# 03_-_PWR_3V3_1V0.net
KiCad netlist of a schematic drawn in Altium Designer
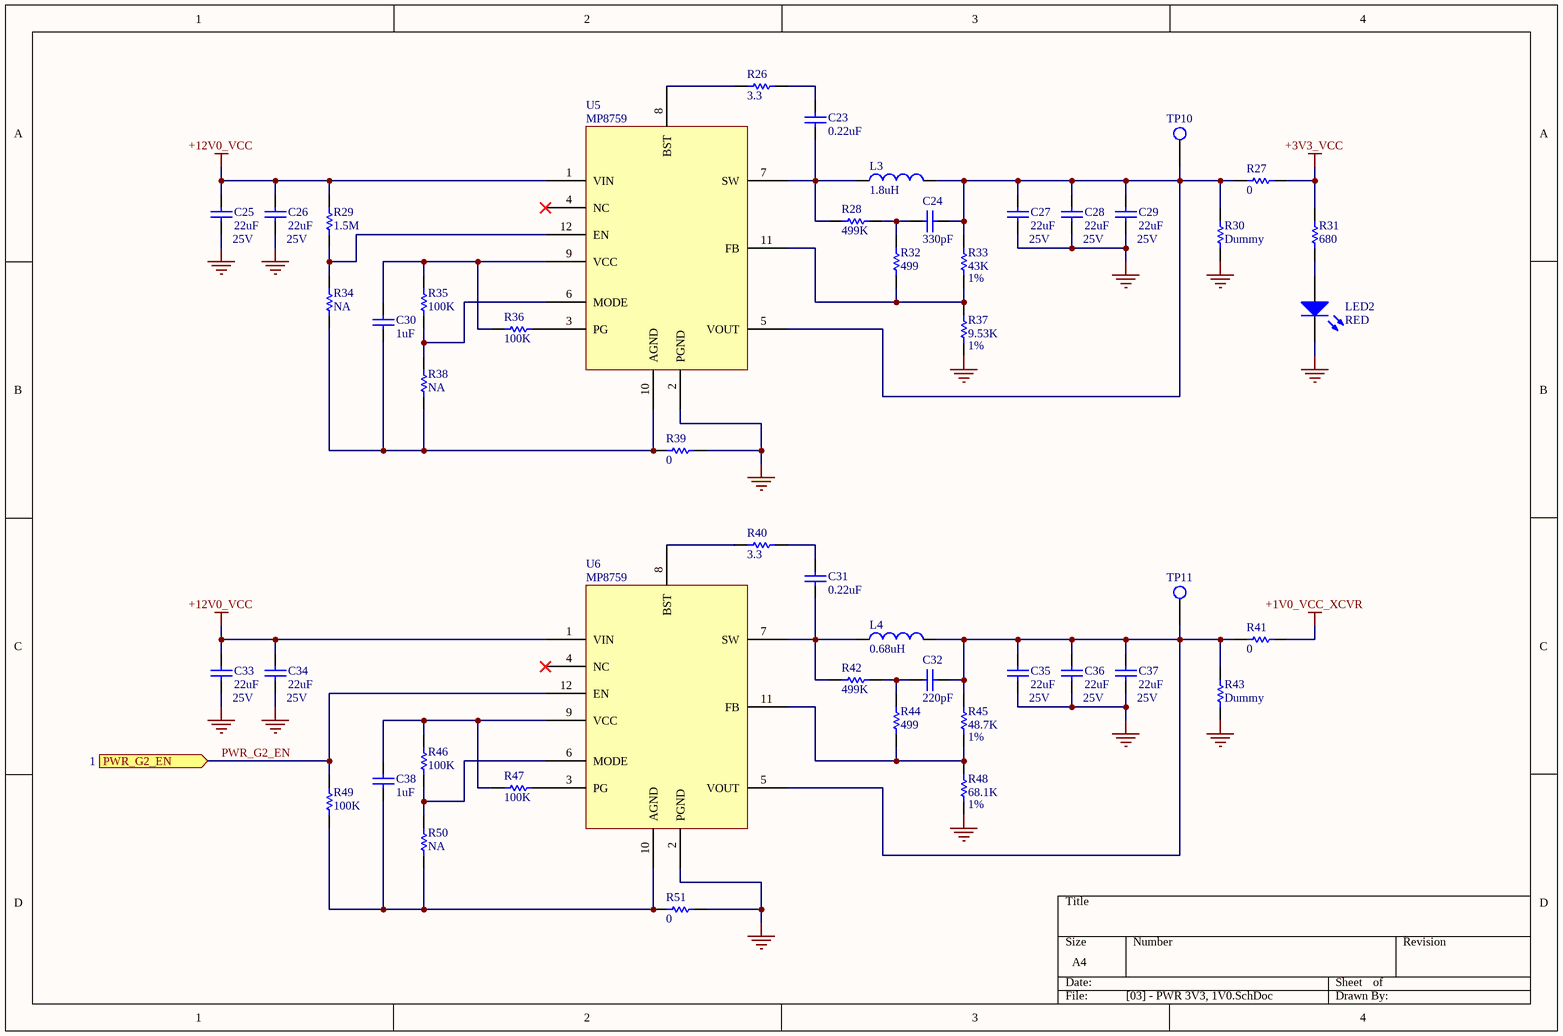
[diagram p0: [03] - PWR 3V3, 1V0.SchDoc]

(export (version "E")
  (design (tool "Eeschema 10.0.6"))
  (components
    (comp (ref "C23")
      (value "0.22uF")
      (footprint "0402_C")
      (description "Non-Pol SMD Capacitor")
      (libsource (lib "Passive Components") (part "Cap SMD"))
    )
    (comp (ref "C24")
      (value "330pF")
      (footprint "0402_C")
      (description "Non-Pol SMD Capacitor")
      (libsource (lib "Passive Components") (part "Cap SMD"))
    )
    (comp (ref "C25")
      (value "22uF")
      (footprint "1210_C")
      (description "Non-Pol SMD Capacitor")
      (fields (field (name "RATED_VOLTAGE") "25V") (field (name "MANUFACTURER PART NUM") "GRM32ER71E226KE15"))
      (libsource (lib "Passive Components") (part "Cap SMD"))
    )
    (comp (ref "C26")
      (value "22uF")
      (footprint "1210_C")
      (description "Non-Pol SMD Capacitor")
      (fields (field (name "RATED_VOLTAGE") "25V") (field (name "MANUFACTURER PART NUM") "GRM32ER71E226KE15"))
      (libsource (lib "Passive Components") (part "Cap SMD"))
    )
    (comp (ref "C27")
      (value "22uF")
      (footprint "1210_C")
      (description "Non-Pol SMD Capacitor")
      (fields (field (name "RATED_VOLTAGE") "25V") (field (name "MANUFACTURER PART NUM") "GRM32ER71E226KE15"))
      (libsource (lib "Passive Components") (part "Cap SMD"))
    )
    (comp (ref "C28")
      (value "22uF")
      (footprint "1210_C")
      (description "Non-Pol SMD Capacitor")
      (fields (field (name "RATED_VOLTAGE") "25V") (field (name "MANUFACTURER PART NUM") "GRM32ER71E226KE15"))
      (libsource (lib "Passive Components") (part "Cap SMD"))
    )
    (comp (ref "C29")
      (value "22uF")
      (footprint "1210_C")
      (description "Non-Pol SMD Capacitor")
      (fields (field (name "RATED_VOLTAGE") "25V") (field (name "MANUFACTURER PART NUM") "GRM32ER71E226KE15"))
      (libsource (lib "Passive Components") (part "Cap SMD"))
    )
    (comp (ref "C30")
      (value "1uF")
      (footprint "0402_C")
      (description "Non-Pol SMD Capacitor")
      (fields (field (name "MANUFACTURER PART NUM") "GCM155C71A105ME38"))
      (libsource (lib "Passive Components") (part "Cap SMD"))
    )
    (comp (ref "C31")
      (value "0.22uF")
      (footprint "0402_C")
      (description "Non-Pol SMD Capacitor")
      (libsource (lib "Passive Components") (part "Cap SMD"))
    )
    (comp (ref "C32")
      (value "220pF")
      (footprint "0402_C")
      (description "Non-Pol SMD Capacitor")
      (libsource (lib "Passive Components") (part "Cap SMD"))
    )
    (comp (ref "C33")
      (value "22uF")
      (footprint "1210_C")
      (description "Non-Pol SMD Capacitor")
      (fields (field (name "RATED_VOLTAGE") "25V") (field (name "MANUFACTURER PART NUM") "GRM32ER71E226KE15"))
      (libsource (lib "Passive Components") (part "Cap SMD"))
    )
    (comp (ref "C34")
      (value "22uF")
      (footprint "1210_C")
      (description "Non-Pol SMD Capacitor")
      (fields (field (name "RATED_VOLTAGE") "25V") (field (name "MANUFACTURER PART NUM") "GRM32ER71E226KE15"))
      (libsource (lib "Passive Components") (part "Cap SMD"))
    )
    (comp (ref "C35")
      (value "22uF")
      (footprint "1210_C")
      (description "Non-Pol SMD Capacitor")
      (fields (field (name "RATED_VOLTAGE") "25V") (field (name "MANUFACTURER PART NUM") "GRM32ER71E226KE15"))
      (libsource (lib "Passive Components") (part "Cap SMD"))
    )
    (comp (ref "C36")
      (value "22uF")
      (footprint "1210_C")
      (description "Non-Pol SMD Capacitor")
      (fields (field (name "RATED_VOLTAGE") "25V") (field (name "MANUFACTURER PART NUM") "GRM32ER71E226KE15"))
      (libsource (lib "Passive Components") (part "Cap SMD"))
    )
    (comp (ref "C37")
      (value "22uF")
      (footprint "1210_C")
      (description "Non-Pol SMD Capacitor")
      (fields (field (name "RATED_VOLTAGE") "25V") (field (name "MANUFACTURER PART NUM") "GRM32ER71E226KE15"))
      (libsource (lib "Passive Components") (part "Cap SMD"))
    )
    (comp (ref "C38")
      (value "1uF")
      (footprint "0402_C")
      (description "Non-Pol SMD Capacitor")
      (fields (field (name "MANUFACTURER PART NUM") "GCM155C71A105ME38"))
      (libsource (lib "Passive Components") (part "Cap SMD"))
    )
    (comp (ref "L3")
      (value "1.8uH")
      (footprint "IHLP-4040")
      (description "Inductor SMD")
      (fields (field (name "MANUFACTURER PART NUM") "IHLP4040DZER1R8M11"))
      (libsource (lib "Passive Components") (part "Inductor"))
    )
    (comp (ref "L4")
      (value "0.68uH")
      (footprint "IHLP-2525")
      (description "Inductor SMD")
      (fields (field (name "MANUFACTURER PART NUM") "IHLP2525CZERR68M01"))
      (libsource (lib "Passive Components") (part "Inductor"))
    )
    (comp (ref "LED2")
      (value "RED")
      (footprint "LED_0805")
      (description "Typical LED")
      (libsource (lib "Common Components") (part "LED"))
    )
    (comp (ref "R26")
      (value "3.3")
      (footprint "0402_R")
      (description "SMD Resistor")
      (fields (field (name "TOLERANCE") "5%"))
      (libsource (lib "Passive Components") (part "Res SMD"))
    )
    (comp (ref "R27")
      (value "0")
      (footprint "1210_R")
      (description "SMD Resistor")
      (fields (field (name "TOLERANCE") "5%"))
      (libsource (lib "Passive Components") (part "Res SMD"))
    )
    (comp (ref "R28")
      (value "499K")
      (footprint "0402_R")
      (description "SMD Resistor")
      (fields (field (name "TOLERANCE") "1%"))
      (libsource (lib "Passive Components") (part "Res SMD"))
    )
    (comp (ref "R29")
      (value "1.5M")
      (footprint "0402_R")
      (description "SMD Resistor")
      (fields (field (name "TOLERANCE") "5%"))
      (libsource (lib "Passive Components") (part "Res SMD"))
    )
    (comp (ref "R30")
      (value "Dummy")
      (footprint "1210_R")
      (description "SMD Resistor")
      (fields (field (name "TOLERANCE") "5%"))
      (libsource (lib "Passive Components") (part "Res SMD"))
    )
    (comp (ref "R31")
      (value "680")
      (footprint "0805_R")
      (description "SMD Resistor")
      (fields (field (name "TOLERANCE") "5%"))
      (libsource (lib "Passive Components") (part "Res SMD"))
    )
    (comp (ref "R32")
      (value "499")
      (footprint "0402_R")
      (description "SMD Resistor")
      (fields (field (name "TOLERANCE") "1%"))
      (libsource (lib "Passive Components") (part "Res SMD"))
    )
    (comp (ref "R33")
      (value "43K")
      (footprint "0402_R")
      (description "SMD Resistor")
      (fields (field (name "TOLERANCE") "1%"))
      (libsource (lib "Passive Components") (part "Res SMD"))
    )
    (comp (ref "R34")
      (value "NA")
      (footprint "0402_R")
      (description "SMD Resistor")
      (fields (field (name "TOLERANCE") "5%"))
      (libsource (lib "Passive Components") (part "Res SMD"))
    )
    (comp (ref "R35")
      (value "100K")
      (footprint "0402_R")
      (description "SMD Resistor")
      (fields (field (name "TOLERANCE") "5%"))
      (libsource (lib "Passive Components") (part "Res SMD"))
    )
    (comp (ref "R36")
      (value "100K")
      (footprint "0402_R")
      (description "SMD Resistor")
      (fields (field (name "TOLERANCE") "5%"))
      (libsource (lib "Passive Components") (part "Res SMD"))
    )
    (comp (ref "R37")
      (value "9.53K")
      (footprint "0402_R")
      (description "SMD Resistor")
      (fields (field (name "TOLERANCE") "1%"))
      (libsource (lib "Passive Components") (part "Res SMD"))
    )
    (comp (ref "R38")
      (value "NA")
      (footprint "0402_R")
      (description "SMD Resistor")
      (fields (field (name "TOLERANCE") "5%"))
      (libsource (lib "Passive Components") (part "Res SMD"))
    )
    (comp (ref "R39")
      (value "0")
      (footprint "0402_R")
      (description "SMD Resistor")
      (fields (field (name "TOLERANCE") "5%"))
      (libsource (lib "Passive Components") (part "Res SMD"))
    )
    (comp (ref "R40")
      (value "3.3")
      (footprint "0402_R")
      (description "SMD Resistor")
      (fields (field (name "TOLERANCE") "5%"))
      (libsource (lib "Passive Components") (part "Res SMD"))
    )
    (comp (ref "R41")
      (value "0")
      (footprint "1210_R")
      (description "SMD Resistor")
      (fields (field (name "TOLERANCE") "5%"))
      (libsource (lib "Passive Components") (part "Res SMD"))
    )
    (comp (ref "R42")
      (value "499K")
      (footprint "0402_R")
      (description "SMD Resistor")
      (fields (field (name "TOLERANCE") "1%"))
      (libsource (lib "Passive Components") (part "Res SMD"))
    )
    (comp (ref "R43")
      (value "Dummy")
      (footprint "1210_R")
      (description "SMD Resistor")
      (fields (field (name "TOLERANCE") "5%"))
      (libsource (lib "Passive Components") (part "Res SMD"))
    )
    (comp (ref "R44")
      (value "499")
      (footprint "0402_R")
      (description "SMD Resistor")
      (fields (field (name "TOLERANCE") "1%"))
      (libsource (lib "Passive Components") (part "Res SMD"))
    )
    (comp (ref "R45")
      (value "48.7K")
      (footprint "0402_R")
      (description "SMD Resistor")
      (fields (field (name "TOLERANCE") "1%"))
      (libsource (lib "Passive Components") (part "Res SMD"))
    )
    (comp (ref "R46")
      (value "100K")
      (footprint "0402_R")
      (description "SMD Resistor")
      (fields (field (name "TOLERANCE") "5%"))
      (libsource (lib "Passive Components") (part "Res SMD"))
    )
    (comp (ref "R47")
      (value "100K")
      (footprint "0402_R")
      (description "SMD Resistor")
      (fields (field (name "TOLERANCE") "5%"))
      (libsource (lib "Passive Components") (part "Res SMD"))
    )
    (comp (ref "R48")
      (value "68.1K")
      (footprint "0402_R")
      (description "SMD Resistor")
      (fields (field (name "TOLERANCE") "1%"))
      (libsource (lib "Passive Components") (part "Res SMD"))
    )
    (comp (ref "R49")
      (value "100K")
      (footprint "0402_R")
      (description "SMD Resistor")
      (fields (field (name "TOLERANCE") "5%"))
      (libsource (lib "Passive Components") (part "Res SMD"))
    )
    (comp (ref "R50")
      (value "NA")
      (footprint "0402_R")
      (description "SMD Resistor")
      (fields (field (name "TOLERANCE") "5%"))
      (libsource (lib "Passive Components") (part "Res SMD"))
    )
    (comp (ref "R51")
      (value "0")
      (footprint "0402_R")
      (description "SMD Resistor")
      (fields (field (name "TOLERANCE") "5%"))
      (libsource (lib "Passive Components") (part "Res SMD"))
    )
    (comp (ref "TP10")
      (value "Test Point")
      (footprint "PIN_1.5mm")
      (description "Test Point Footprint")
      (libsource (lib "Passive Components") (part "Test Point"))
    )
    (comp (ref "TP11")
      (value "Test Point")
      (footprint "PIN_1.5mm")
      (description "Test Point Footprint")
      (libsource (lib "Passive Components") (part "Test Point"))
    )
    (comp (ref "U5")
      (value "MP8759")
      (description "26V, 8A, Low I Q , High-Current,  Synchronous, Step-Down Converter")
      (fields (field (name "MANUFACTURER PART NUM") "MP8759GD"))
      (libsource (lib "Project_schlib") (part "MP8759"))
    )
    (comp (ref "U6")
      (value "MP8759")
      (description "26V, 8A, Low I Q , High-Current,  Synchronous, Step-Down Converter")
      (fields (field (name "MANUFACTURER PART NUM") "MP8759GD"))
      (libsource (lib "Project_schlib") (part "MP8759"))
    )
  )
  (nets
    (net (code "1") (name "+1V0_VCC_XCVR") (class "Default")
      (node (ref "R41") (pin "2") (pinfunction "2_2") (pintype "passive"))
    )
    (net (code "2") (name "+3V3_VCC") (class "Default")
      (node (ref "R27") (pin "2") (pinfunction "2_2") (pintype "passive"))
      (node (ref "R31") (pin "2") (pinfunction "2_2") (pintype "passive"))
    )
    (net (code "3") (name "+12V0_VCC") (class "Default")
      (node (ref "C25") (pin "2") (pinfunction "2_2") (pintype "passive"))
      (node (ref "C26") (pin "2") (pinfunction "2_2") (pintype "passive"))
      (node (ref "C33") (pin "2") (pinfunction "2_2") (pintype "passive"))
      (node (ref "C34") (pin "2") (pinfunction "2_2") (pintype "passive"))
      (node (ref "R29") (pin "1") (pinfunction "1_1") (pintype "passive"))
      (node (ref "U5") (pin "1") (pinfunction "VIN_1") (pintype "passive"))
      (node (ref "U6") (pin "1") (pinfunction "VIN_1") (pintype "passive"))
    )
    (net (code "4") (name "/PWR_G2_EN") (class "Default")
      (node (ref "R49") (pin "1") (pinfunction "1_1") (pintype "passive"))
      (node (ref "U6") (pin "12") (pinfunction "EN_12") (pintype "passive"))
    )
    (net (code "5") (name "GND") (class "Default")
      (node (ref "C25") (pin "1") (pinfunction "1_1") (pintype "passive"))
      (node (ref "C26") (pin "1") (pinfunction "1_1") (pintype "passive"))
      (node (ref "C27") (pin "1") (pinfunction "1_1") (pintype "passive"))
      (node (ref "C28") (pin "1") (pinfunction "1_1") (pintype "passive"))
      (node (ref "C29") (pin "1") (pinfunction "1_1") (pintype "passive"))
      (node (ref "C33") (pin "1") (pinfunction "1_1") (pintype "passive"))
      (node (ref "C34") (pin "1") (pinfunction "1_1") (pintype "passive"))
      (node (ref "C35") (pin "1") (pinfunction "1_1") (pintype "passive"))
      (node (ref "C36") (pin "1") (pinfunction "1_1") (pintype "passive"))
      (node (ref "C37") (pin "1") (pinfunction "1_1") (pintype "passive"))
      (node (ref "LED2") (pin "2") (pinfunction "K_2") (pintype "passive"))
      (node (ref "R30") (pin "1") (pinfunction "1_1") (pintype "passive"))
      (node (ref "R37") (pin "1") (pinfunction "1_1") (pintype "passive"))
      (node (ref "R39") (pin "1") (pinfunction "1_1") (pintype "passive"))
      (node (ref "R43") (pin "1") (pinfunction "1_1") (pintype "passive"))
      (node (ref "R48") (pin "1") (pinfunction "1_1") (pintype "passive"))
      (node (ref "R51") (pin "1") (pinfunction "1_1") (pintype "passive"))
      (node (ref "U5") (pin "2") (pinfunction "PGND_2") (pintype "passive"))
      (node (ref "U6") (pin "2") (pinfunction "PGND_2") (pintype "passive"))
    )
    (net (code "6") (name "Net-(C23-Pad2)") (class "Default")
      (node (ref "C23") (pin "2") (pinfunction "2_2") (pintype "passive"))
      (node (ref "R26") (pin "2") (pinfunction "2_2") (pintype "passive"))
    )
    (net (code "7") (name "Net-(C24-Pad2)") (class "Default")
      (node (ref "C24") (pin "2") (pinfunction "2_2") (pintype "passive"))
      (node (ref "R28") (pin "1") (pinfunction "1_1") (pintype "passive"))
      (node (ref "R32") (pin "1") (pinfunction "1_1") (pintype "passive"))
    )
    (net (code "8") (name "Net-(C31-Pad2)") (class "Default")
      (node (ref "C31") (pin "2") (pinfunction "2_2") (pintype "passive"))
      (node (ref "R40") (pin "2") (pinfunction "2_2") (pintype "passive"))
    )
    (net (code "9") (name "Net-(C32-Pad2)") (class "Default")
      (node (ref "C32") (pin "2") (pinfunction "2_2") (pintype "passive"))
      (node (ref "R42") (pin "1") (pinfunction "1_1") (pintype "passive"))
      (node (ref "R44") (pin "1") (pinfunction "1_1") (pintype "passive"))
    )
    (net (code "10") (name "Net-(LED2-A)") (class "Default")
      (node (ref "LED2") (pin "1") (pinfunction "A_1") (pintype "passive"))
      (node (ref "R31") (pin "1") (pinfunction "1_1") (pintype "passive"))
    )
    (net (code "11") (name "Net-(U5-AGND)") (class "Default")
      (node (ref "C30") (pin "1") (pinfunction "1_1") (pintype "passive"))
      (node (ref "R34") (pin "2") (pinfunction "2_2") (pintype "passive"))
      (node (ref "R38") (pin "2") (pinfunction "2_2") (pintype "passive"))
      (node (ref "R39") (pin "2") (pinfunction "2_2") (pintype "passive"))
      (node (ref "U5") (pin "10") (pinfunction "AGND_10") (pintype "passive"))
    )
    (net (code "12") (name "Net-(U5-BST)") (class "Default")
      (node (ref "R26") (pin "1") (pinfunction "1_1") (pintype "passive"))
      (node (ref "U5") (pin "8") (pinfunction "BST_8") (pintype "passive"))
    )
    (net (code "13") (name "Net-(U5-EN)") (class "Default")
      (node (ref "R29") (pin "2") (pinfunction "2_2") (pintype "passive"))
      (node (ref "R34") (pin "1") (pinfunction "1_1") (pintype "passive"))
      (node (ref "U5") (pin "12") (pinfunction "EN_12") (pintype "passive"))
    )
    (net (code "14") (name "Net-(U5-FB)") (class "Default")
      (node (ref "R32") (pin "2") (pinfunction "2_2") (pintype "passive"))
      (node (ref "R33") (pin "1") (pinfunction "1_1") (pintype "passive"))
      (node (ref "R37") (pin "2") (pinfunction "2_2") (pintype "passive"))
      (node (ref "U5") (pin "11") (pinfunction "FB_11") (pintype "passive"))
    )
    (net (code "15") (name "Net-(U5-MODE)") (class "Default")
      (node (ref "R35") (pin "2") (pinfunction "2_2") (pintype "passive"))
      (node (ref "R38") (pin "1") (pinfunction "1_1") (pintype "passive"))
      (node (ref "U5") (pin "6") (pinfunction "MODE_6") (pintype "passive"))
    )
    (net (code "16") (name "Net-(U5-PG)") (class "Default")
      (node (ref "R36") (pin "1") (pinfunction "1_1") (pintype "passive"))
      (node (ref "U5") (pin "3") (pinfunction "PG_3") (pintype "passive"))
    )
    (net (code "17") (name "Net-(U5-SW)") (class "Default")
      (node (ref "C23") (pin "1") (pinfunction "1_1") (pintype "passive"))
      (node (ref "L3") (pin "1") (pinfunction "1_1") (pintype "passive"))
      (node (ref "R28") (pin "2") (pinfunction "2_2") (pintype "passive"))
      (node (ref "U5") (pin "7") (pinfunction "SW_7") (pintype "passive"))
    )
    (net (code "18") (name "Net-(U5-VCC)") (class "Default")
      (node (ref "C30") (pin "2") (pinfunction "2_2") (pintype "passive"))
      (node (ref "R35") (pin "1") (pinfunction "1_1") (pintype "passive"))
      (node (ref "R36") (pin "2") (pinfunction "2_2") (pintype "passive"))
      (node (ref "U5") (pin "9") (pinfunction "VCC_9") (pintype "passive"))
    )
    (net (code "19") (name "Net-(U5-VOUT)") (class "Default")
      (node (ref "C24") (pin "1") (pinfunction "1_1") (pintype "passive"))
      (node (ref "C27") (pin "2") (pinfunction "2_2") (pintype "passive"))
      (node (ref "C28") (pin "2") (pinfunction "2_2") (pintype "passive"))
      (node (ref "C29") (pin "2") (pinfunction "2_2") (pintype "passive"))
      (node (ref "L3") (pin "2") (pinfunction "2_2") (pintype "passive"))
      (node (ref "R27") (pin "1") (pinfunction "1_1") (pintype "passive"))
      (node (ref "R30") (pin "2") (pinfunction "2_2") (pintype "passive"))
      (node (ref "R33") (pin "2") (pinfunction "2_2") (pintype "passive"))
      (node (ref "TP10") (pin "1") (pinfunction "1_1") (pintype "passive"))
      (node (ref "U5") (pin "5") (pinfunction "VOUT_5") (pintype "passive"))
    )
    (net (code "20") (name "Net-(U6-AGND)") (class "Default")
      (node (ref "C38") (pin "1") (pinfunction "1_1") (pintype "passive"))
      (node (ref "R49") (pin "2") (pinfunction "2_2") (pintype "passive"))
      (node (ref "R50") (pin "2") (pinfunction "2_2") (pintype "passive"))
      (node (ref "R51") (pin "2") (pinfunction "2_2") (pintype "passive"))
      (node (ref "U6") (pin "10") (pinfunction "AGND_10") (pintype "passive"))
    )
    (net (code "21") (name "Net-(U6-BST)") (class "Default")
      (node (ref "R40") (pin "1") (pinfunction "1_1") (pintype "passive"))
      (node (ref "U6") (pin "8") (pinfunction "BST_8") (pintype "passive"))
    )
    (net (code "22") (name "Net-(U6-FB)") (class "Default")
      (node (ref "R44") (pin "2") (pinfunction "2_2") (pintype "passive"))
      (node (ref "R45") (pin "1") (pinfunction "1_1") (pintype "passive"))
      (node (ref "R48") (pin "2") (pinfunction "2_2") (pintype "passive"))
      (node (ref "U6") (pin "11") (pinfunction "FB_11") (pintype "passive"))
    )
    (net (code "23") (name "Net-(U6-MODE)") (class "Default")
      (node (ref "R46") (pin "2") (pinfunction "2_2") (pintype "passive"))
      (node (ref "R50") (pin "1") (pinfunction "1_1") (pintype "passive"))
      (node (ref "U6") (pin "6") (pinfunction "MODE_6") (pintype "passive"))
    )
    (net (code "24") (name "Net-(U6-PG)") (class "Default")
      (node (ref "R47") (pin "1") (pinfunction "1_1") (pintype "passive"))
      (node (ref "U6") (pin "3") (pinfunction "PG_3") (pintype "passive"))
    )
    (net (code "25") (name "Net-(U6-SW)") (class "Default")
      (node (ref "C31") (pin "1") (pinfunction "1_1") (pintype "passive"))
      (node (ref "L4") (pin "1") (pinfunction "1_1") (pintype "passive"))
      (node (ref "R42") (pin "2") (pinfunction "2_2") (pintype "passive"))
      (node (ref "U6") (pin "7") (pinfunction "SW_7") (pintype "passive"))
    )
    (net (code "26") (name "Net-(U6-VCC)") (class "Default")
      (node (ref "C38") (pin "2") (pinfunction "2_2") (pintype "passive"))
      (node (ref "R46") (pin "1") (pinfunction "1_1") (pintype "passive"))
      (node (ref "R47") (pin "2") (pinfunction "2_2") (pintype "passive"))
      (node (ref "U6") (pin "9") (pinfunction "VCC_9") (pintype "passive"))
    )
    (net (code "27") (name "Net-(U6-VOUT)") (class "Default")
      (node (ref "C32") (pin "1") (pinfunction "1_1") (pintype "passive"))
      (node (ref "C35") (pin "2") (pinfunction "2_2") (pintype "passive"))
      (node (ref "C36") (pin "2") (pinfunction "2_2") (pintype "passive"))
      (node (ref "C37") (pin "2") (pinfunction "2_2") (pintype "passive"))
      (node (ref "L4") (pin "2") (pinfunction "2_2") (pintype "passive"))
      (node (ref "R41") (pin "1") (pinfunction "1_1") (pintype "passive"))
      (node (ref "R43") (pin "2") (pinfunction "2_2") (pintype "passive"))
      (node (ref "R45") (pin "2") (pinfunction "2_2") (pintype "passive"))
      (node (ref "TP11") (pin "1") (pinfunction "1_1") (pintype "passive"))
      (node (ref "U6") (pin "5") (pinfunction "VOUT_5") (pintype "passive"))
    )
    (net (code "28") (name "unconnected-(U5-NC-Pad4)") (class "Default")
      (node (ref "U5") (pin "4") (pinfunction "NC_4") (pintype "passive+no_connect"))
    )
    (net (code "29") (name "unconnected-(U6-NC-Pad4)") (class "Default")
      (node (ref "U6") (pin "4") (pinfunction "NC_4") (pintype "passive+no_connect"))
    )
  )
)
